# roast-pcb.net
KiCad netlist of a schematic drawn in EAGLE
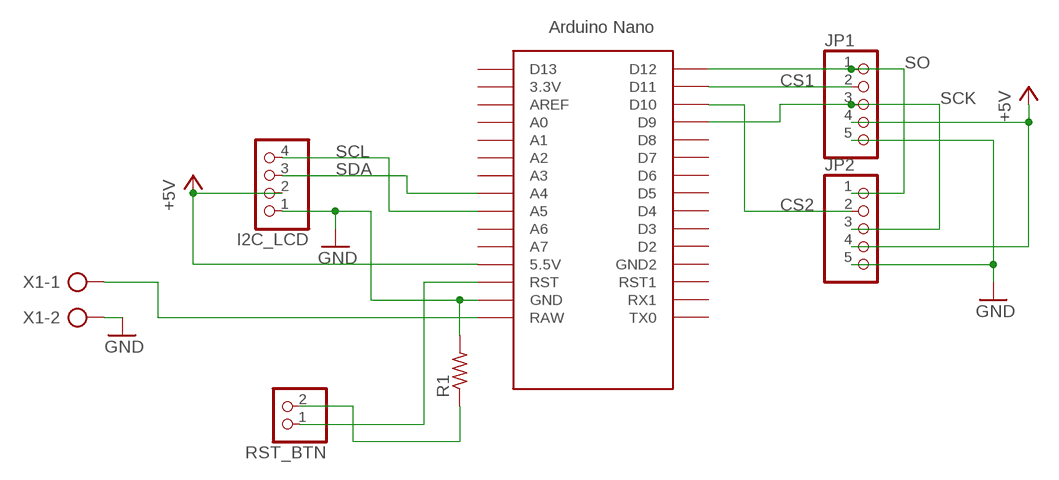
[diagram p0: schematic, sheet 1]

(export (version "E")
  (design (tool "Eeschema 10.0.6"))
  (components
    (comp (ref "I2C_LCD")
      (value "PINHD-1X4")
      (footprint "eagle-import:1X04")
      (libsource (lib "eagle-import") (part "PINHD-1X4"))
    )
    (comp (ref "JP1")
      (value "PINHD-1X5")
      (footprint "eagle-import:1X05")
      (libsource (lib "eagle-import") (part "PINHD-1X5"))
    )
    (comp (ref "JP2")
      (value "PINHD-1X5")
      (footprint "eagle-import:1X05")
      (libsource (lib "eagle-import") (part "PINHD-1X5"))
    )
    (comp (ref "R1")
      (value "R-US_0207/10")
      (footprint "eagle-import:0207_10")
      (libsource (lib "eagle-import") (part "R-US_0207/10"))
    )
    (comp (ref "RST_BTN")
      (value "PINHD-1X2")
      (footprint "eagle-import:1X02")
      (libsource (lib "eagle-import") (part "PINHD-1X2"))
    )
    (comp (ref "U$1")
      (value "NANO")
      (footprint "eagle-import:NANO")
      (libsource (lib "eagle-import") (part "NANO"))
    )
    (comp (ref "X1")
      (value "AK300/2")
      (footprint "eagle-import:AK300_2")
      (libsource (lib "eagle-import") (part "AK300/2"))
    )
  )
  (nets
    (net (code "1") (name "+5V") (class "Default")
      (node (ref "I2C_LCD") (pin "2") (pinfunction "2_2") (pintype "passive"))
      (node (ref "JP1") (pin "4") (pinfunction "4_4") (pintype "passive"))
      (node (ref "JP2") (pin "4") (pinfunction "4_4") (pintype "passive"))
      (node (ref "U$1") (pin "5V") (pinfunction "5.5V_5V") (pintype "bidirectional"))
    )
    (net (code "2") (name "/CS1") (class "Default")
      (node (ref "JP1") (pin "2") (pinfunction "2_2") (pintype "passive"))
      (node (ref "U$1") (pin "D11") (pinfunction "D11_D11") (pintype "bidirectional"))
    )
    (net (code "3") (name "/CS2") (class "Default")
      (node (ref "JP2") (pin "2") (pinfunction "2_2") (pintype "passive"))
      (node (ref "U$1") (pin "D10") (pinfunction "D10_D10") (pintype "bidirectional"))
    )
    (net (code "4") (name "/SCK") (class "Default")
      (node (ref "JP1") (pin "3") (pinfunction "3_3") (pintype "passive"))
      (node (ref "JP2") (pin "3") (pinfunction "3_3") (pintype "passive"))
      (node (ref "U$1") (pin "D9") (pinfunction "D9_D9") (pintype "bidirectional"))
    )
    (net (code "5") (name "/SCL") (class "Default")
      (node (ref "I2C_LCD") (pin "4") (pinfunction "4_4") (pintype "passive"))
      (node (ref "U$1") (pin "A5") (pinfunction "A5_A5") (pintype "bidirectional"))
    )
    (net (code "6") (name "/SDA") (class "Default")
      (node (ref "I2C_LCD") (pin "3") (pinfunction "3_3") (pintype "passive"))
      (node (ref "U$1") (pin "A4") (pinfunction "A4_A4") (pintype "bidirectional"))
    )
    (net (code "7") (name "/SO") (class "Default")
      (node (ref "JP1") (pin "1") (pinfunction "1_1") (pintype "passive"))
      (node (ref "JP2") (pin "1") (pinfunction "1_1") (pintype "passive"))
      (node (ref "U$1") (pin "D12") (pinfunction "D12_D12") (pintype "bidirectional"))
    )
    (net (code "8") (name "GND") (class "Default")
      (node (ref "I2C_LCD") (pin "1") (pinfunction "1_1") (pintype "passive"))
      (node (ref "JP1") (pin "5") (pinfunction "5_5") (pintype "passive"))
      (node (ref "JP2") (pin "5") (pinfunction "5_5") (pintype "passive"))
      (node (ref "R1") (pin "2") (pinfunction "2_2") (pintype "passive"))
      (node (ref "U$1") (pin "GND") (pinfunction "GND_GND") (pintype "bidirectional"))
      (node (ref "X1") (pin "2") (pinfunction "KL_2") (pintype "passive"))
    )
    (net (code "9") (name "Net-(R1-Pad1)") (class "Default")
      (node (ref "R1") (pin "1") (pinfunction "1_1") (pintype "passive"))
      (node (ref "RST_BTN") (pin "2") (pinfunction "2_2") (pintype "passive"))
    )
    (net (code "10") (name "Net-(RST_BTN-Pad1)") (class "Default")
      (node (ref "RST_BTN") (pin "1") (pinfunction "1_1") (pintype "passive"))
      (node (ref "U$1") (pin "RST") (pinfunction "RST_RST") (pintype "bidirectional"))
    )
    (net (code "11") (name "Net-(X1A-KL)") (class "Default")
      (node (ref "U$1") (pin "RAW") (pinfunction "RAW_RAW") (pintype "bidirectional"))
      (node (ref "X1") (pin "1") (pinfunction "KL_1") (pintype "passive"))
    )
    (net (code "12") (name "unconnected-(U$1-GND2-PadGND1)") (class "Default")
      (node (ref "U$1") (pin "GND1") (pinfunction "GND2_GND1") (pintype "bidirectional"))
    )
    (net (code "13") (name "unconnected-(U$1-Pad3.3V)") (class "Default")
      (node (ref "U$1") (pin "3.3V") (pinfunction "3.3V_3.3V") (pintype "bidirectional"))
    )
    (net (code "14") (name "unconnected-(U$1-PadA0)") (class "Default")
      (node (ref "U$1") (pin "A0") (pinfunction "A0_A0") (pintype "bidirectional"))
    )
    (net (code "15") (name "unconnected-(U$1-PadA1)") (class "Default")
      (node (ref "U$1") (pin "A1") (pinfunction "A1_A1") (pintype "bidirectional"))
    )
    (net (code "16") (name "unconnected-(U$1-PadA2)") (class "Default")
      (node (ref "U$1") (pin "A2") (pinfunction "A2_A2") (pintype "bidirectional"))
    )
    (net (code "17") (name "unconnected-(U$1-PadA3)") (class "Default")
      (node (ref "U$1") (pin "A3") (pinfunction "A3_A3") (pintype "bidirectional"))
    )
    (net (code "18") (name "unconnected-(U$1-PadA6)") (class "Default")
      (node (ref "U$1") (pin "A6") (pinfunction "A6_A6") (pintype "bidirectional"))
    )
    (net (code "19") (name "unconnected-(U$1-PadA7)") (class "Default")
      (node (ref "U$1") (pin "A7") (pinfunction "A7_A7") (pintype "bidirectional"))
    )
    (net (code "20") (name "unconnected-(U$1-PadAREF)") (class "Default")
      (node (ref "U$1") (pin "AREF") (pinfunction "AREF_AREF") (pintype "bidirectional"))
    )
    (net (code "21") (name "unconnected-(U$1-PadD2)") (class "Default")
      (node (ref "U$1") (pin "D2") (pinfunction "D2_D2") (pintype "bidirectional"))
    )
    (net (code "22") (name "unconnected-(U$1-PadD3)") (class "Default")
      (node (ref "U$1") (pin "D3") (pinfunction "D3_D3") (pintype "bidirectional"))
    )
    (net (code "23") (name "unconnected-(U$1-PadD4)") (class "Default")
      (node (ref "U$1") (pin "D4") (pinfunction "D4_D4") (pintype "bidirectional"))
    )
    (net (code "24") (name "unconnected-(U$1-PadD5)") (class "Default")
      (node (ref "U$1") (pin "D5") (pinfunction "D5_D5") (pintype "bidirectional"))
    )
    (net (code "25") (name "unconnected-(U$1-PadD6)") (class "Default")
      (node (ref "U$1") (pin "D6") (pinfunction "D6_D6") (pintype "bidirectional"))
    )
    (net (code "26") (name "unconnected-(U$1-PadD7)") (class "Default")
      (node (ref "U$1") (pin "D7") (pinfunction "D7_D7") (pintype "bidirectional"))
    )
    (net (code "27") (name "unconnected-(U$1-PadD8)") (class "Default")
      (node (ref "U$1") (pin "D8") (pinfunction "D8_D8") (pintype "bidirectional"))
    )
    (net (code "28") (name "unconnected-(U$1-PadD13)") (class "Default")
      (node (ref "U$1") (pin "D13") (pinfunction "D13_D13") (pintype "bidirectional"))
    )
    (net (code "29") (name "unconnected-(U$1-PadICSP1)") (class "Default")
      (node (ref "U$1") (pin "ICSP1") (pinfunction "ICSP1_ICSP1") (pintype "bidirectional"))
    )
    (net (code "30") (name "unconnected-(U$1-PadICSP2)") (class "Default")
      (node (ref "U$1") (pin "ICSP2") (pinfunction "ICSP2_ICSP2") (pintype "bidirectional"))
    )
    (net (code "31") (name "unconnected-(U$1-PadICSP3)") (class "Default")
      (node (ref "U$1") (pin "ICSP3") (pinfunction "ICSP3_ICSP3") (pintype "bidirectional"))
    )
    (net (code "32") (name "unconnected-(U$1-PadICSP4)") (class "Default")
      (node (ref "U$1") (pin "ICSP4") (pinfunction "ICSP4_ICSP4") (pintype "bidirectional"))
    )
    (net (code "33") (name "unconnected-(U$1-PadICSP5)") (class "Default")
      (node (ref "U$1") (pin "ICSP5") (pinfunction "ICSP5_ICSP5") (pintype "bidirectional"))
    )
    (net (code "34") (name "unconnected-(U$1-PadICSP6)") (class "Default")
      (node (ref "U$1") (pin "ICSP6") (pinfunction "ICSP6_ICSP6") (pintype "bidirectional"))
    )
    (net (code "35") (name "unconnected-(U$1-PadRST1)") (class "Default")
      (node (ref "U$1") (pin "RST1") (pinfunction "RST1_RST1") (pintype "bidirectional"))
    )
    (net (code "36") (name "unconnected-(U$1-PadRX1)") (class "Default")
      (node (ref "U$1") (pin "RX1") (pinfunction "RX1_RX1") (pintype "bidirectional"))
    )
    (net (code "37") (name "unconnected-(U$1-PadTX0)") (class "Default")
      (node (ref "U$1") (pin "TX0") (pinfunction "TX0_TX0") (pintype "bidirectional"))
    )
  )
)
